# attinier85-batty-shield-mk-1_0.net
KiCad netlist of a schematic drawn in EAGLE
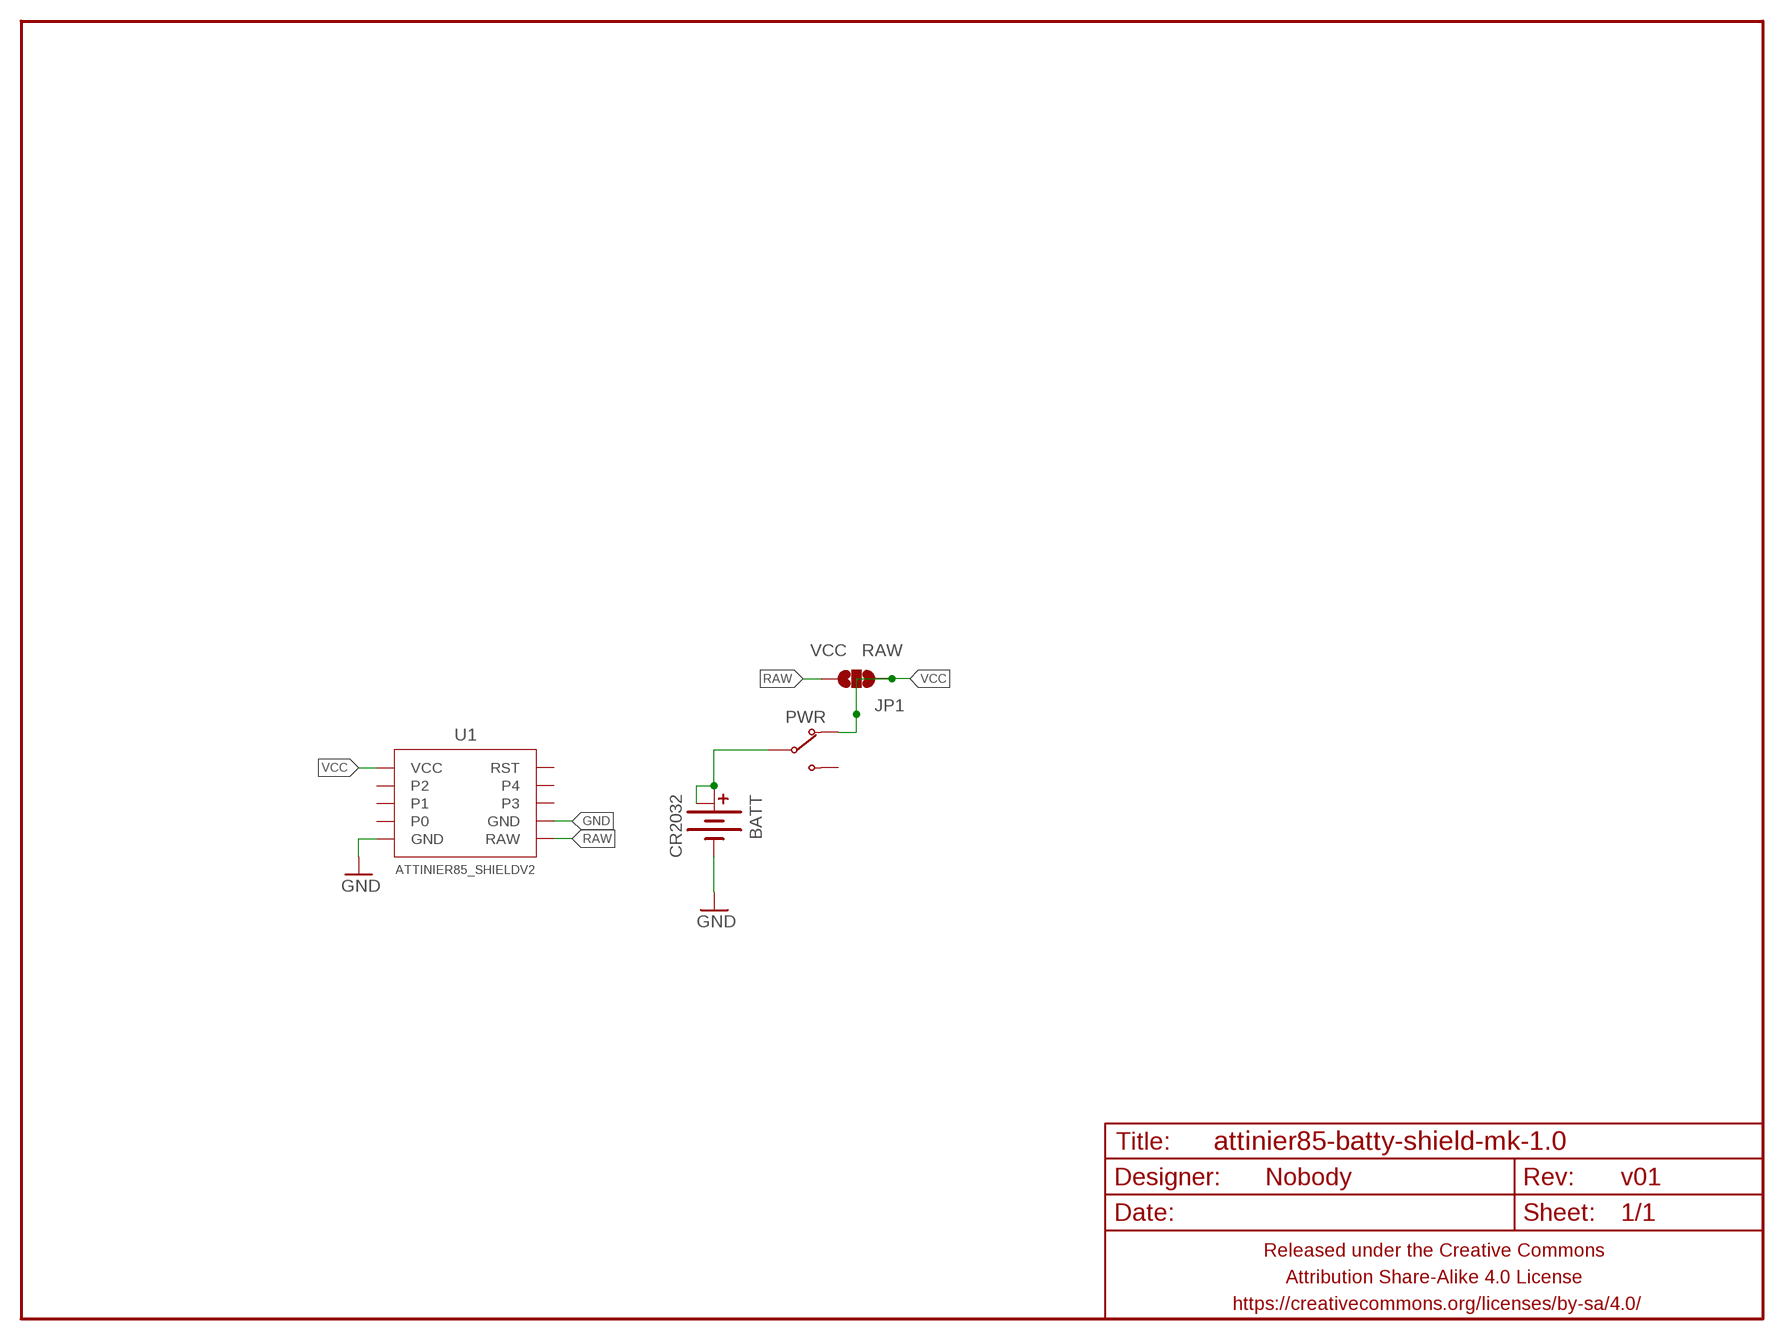
[diagram p0: schematic, sheet 1]

(export (version "E")
  (design (tool "Eeschema 10.0.6"))
  (components
    (comp (ref "BATT")
      (value "CR2032")
      (footprint "eagle-import:BATTCON_20MM_MINE")
      (libsource (lib "eagle-import") (part "BATTERY-COINCR2032_SMD"))
    )
    (comp (ref "FRAME1")
      (value "FRAME-LETTERNO_PACKAGE")
      (footprint "eagle-import:DUMMY")
      (fields (field (name "DESIGNER") "Nobody"))
      (libsource (lib "eagle-import") (part "FRAME-LETTERNO_PACKAGE"))
    )
    (comp (ref "JP1")
      (value "VCC RAW")
      (footprint "eagle-import:PAD-JUMPER-3-NO_YES_SILK_FULL_BOX")
      (libsource (lib "eagle-import") (part "JUMPER-PAD-3-NOFULL_BOX_SILK"))
    )
    (comp (ref "PWR")
      (value "SWITCH-SPDTPTH-RA-2MM")
      (footprint "eagle-import:SPDT-RA-2MM")
      (libsource (lib "eagle-import") (part "SWITCH-SPDTPTH-RA-2MM"))
    )
    (comp (ref "U1")
      (value "ATTINIER85_SHIELDV2")
      (footprint "eagle-import:ATTINIER85_SHIELD_V2")
      (libsource (lib "eagle-import") (part "ATTINIER85_SHIELDV2"))
    )
  )
  (nets
    (net (code "1") (name "GND") (class "Default")
      (node (ref "BATT") (pin "BOTTOM") (pinfunction "-_BOTTOM") (pintype "bidirectional"))
      (node (ref "U1") (pin "GND@1") (pinfunction "GND_GND@1") (pintype "bidirectional"))
      (node (ref "U1") (pin "GND@2") (pinfunction "GND_GND@2") (pintype "bidirectional"))
    )
    (net (code "2") (name "Net-(BATT-+)") (class "Default")
      (node (ref "BATT") (pin "TOP@1") (pinfunction "+_TOP@1") (pintype "bidirectional"))
      (node (ref "BATT") (pin "TOP@2") (pinfunction "+1_TOP@2") (pintype "bidirectional"))
      (node (ref "PWR") (pin "2") (pinfunction "COM_2") (pintype "passive"))
    )
    (net (code "3") (name "RAW") (class "Default")
      (node (ref "JP1") (pin "1") (pinfunction "1_1") (pintype "passive"))
      (node (ref "U1") (pin "RAW") (pinfunction "RAW_RAW") (pintype "bidirectional"))
    )
    (net (code "4") (name "VCC") (class "Default")
      (node (ref "JP1") (pin "2") (pinfunction "2_2") (pintype "passive"))
      (node (ref "JP1") (pin "3") (pinfunction "3_3") (pintype "passive"))
      (node (ref "PWR") (pin "1") (pinfunction "NC_1") (pintype "passive"))
      (node (ref "U1") (pin "VCC") (pinfunction "VCC_VCC") (pintype "bidirectional"))
    )
    (net (code "5") (name "unconnected-(PWR-NO-Pad3)") (class "Default")
      (node (ref "PWR") (pin "3") (pinfunction "NO_3") (pintype "passive"))
    )
    (net (code "6") (name "unconnected-(U1-P0-Pad0)") (class "Default")
      (node (ref "U1") (pin "0") (pinfunction "P0_0") (pintype "bidirectional"))
    )
    (net (code "7") (name "unconnected-(U1-P1-Pad1)") (class "Default")
      (node (ref "U1") (pin "1") (pinfunction "P1_1") (pintype "bidirectional"))
    )
    (net (code "8") (name "unconnected-(U1-P2-Pad2)") (class "Default")
      (node (ref "U1") (pin "2") (pinfunction "P2_2") (pintype "bidirectional"))
    )
    (net (code "9") (name "unconnected-(U1-P3-Pad3)") (class "Default")
      (node (ref "U1") (pin "3") (pinfunction "P3_3") (pintype "bidirectional"))
    )
    (net (code "10") (name "unconnected-(U1-P4-Pad4)") (class "Default")
      (node (ref "U1") (pin "4") (pinfunction "P4_4") (pintype "bidirectional"))
    )
    (net (code "11") (name "unconnected-(U1-PadRST)") (class "Default")
      (node (ref "U1") (pin "RST") (pinfunction "RST_RST") (pintype "bidirectional"))
    )
  )
)
